# ZYNQ400-CONDIP.net
KiCad netlist of a schematic drawn in Altium Designer
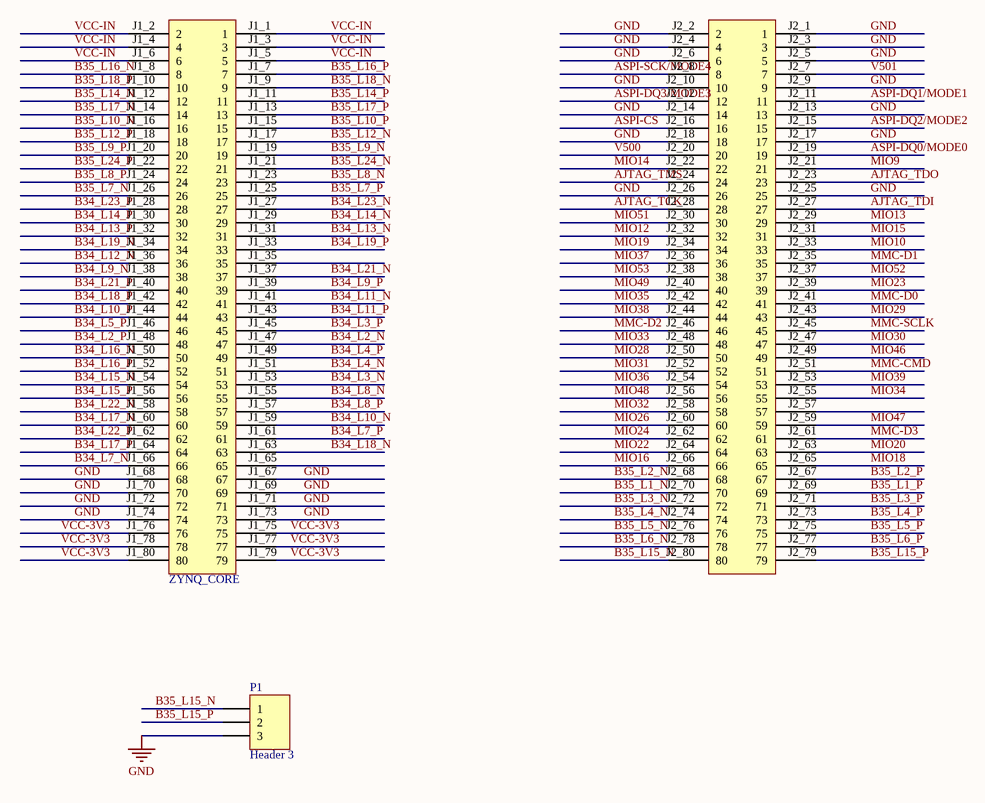
[diagram p0: ZYNQ400-CONDIP.SchDoc]

(export (version "E")
  (design (tool "Eeschema 10.0.6"))
  (components
    (comp (ref "M1")
      (value "ZYNQ_CORE")
      (footprint "ZYNQ7010&7020")
      (description "ZYNQ7010&7020 Core Board")
      (libsource (lib "ZYNQ领航者底板") (part "ZYNQ7010&7020"))
    )
    (comp (ref "P1")
      (value "Header 3")
      (footprint "HDR1X3")
      (description "Header, 3-Pin")
      (fields (field (name "PUBLISHER") "Altium Limited"))
      (libsource (lib "Miscellaneous Connectors") (part "Header 3"))
    )
  )
  (nets
    (net (code "1") (name "/AJTAG_TCK") (class "Default")
      (node (ref "M1") (pin "J2_28") (pinfunction "28_J2_28") (pintype "passive"))
    )
    (net (code "2") (name "/AJTAG_TDI") (class "Default")
      (node (ref "M1") (pin "J2_27") (pinfunction "27_J2_27") (pintype "passive"))
    )
    (net (code "3") (name "/AJTAG_TDO") (class "Default")
      (node (ref "M1") (pin "J2_23") (pinfunction "23_J2_23") (pintype "passive"))
    )
    (net (code "4") (name "/AJTAG_TMS") (class "Default")
      (node (ref "M1") (pin "J2_24") (pinfunction "24_J2_24") (pintype "passive"))
    )
    (net (code "5") (name "/ASPI-CS") (class "Default")
      (node (ref "M1") (pin "J2_16") (pinfunction "16_J2_16") (pintype "passive"))
    )
    (net (code "6") (name "/ASPI-DQ0{slash}MODE0") (class "Default")
      (node (ref "M1") (pin "J2_19") (pinfunction "19_J2_19") (pintype "passive"))
    )
    (net (code "7") (name "/ASPI-DQ1{slash}MODE1") (class "Default")
      (node (ref "M1") (pin "J2_11") (pinfunction "11_J2_11") (pintype "passive"))
    )
    (net (code "8") (name "/ASPI-DQ2{slash}MODE2") (class "Default")
      (node (ref "M1") (pin "J2_15") (pinfunction "15_J2_15") (pintype "passive"))
    )
    (net (code "9") (name "/ASPI-DQ3{slash}MODE3") (class "Default")
      (node (ref "M1") (pin "J2_12") (pinfunction "12_J2_12") (pintype "passive"))
    )
    (net (code "10") (name "/ASPI-SCK{slash}MODE4") (class "Default")
      (node (ref "M1") (pin "J2_8") (pinfunction "8_J2_8") (pintype "passive"))
    )
    (net (code "11") (name "/B34_L2_N") (class "Default")
      (node (ref "M1") (pin "J1_47") (pinfunction "47_J1_47") (pintype "passive"))
    )
    (net (code "12") (name "/B34_L2_P") (class "Default")
      (node (ref "M1") (pin "J1_48") (pinfunction "48_J1_48") (pintype "passive"))
    )
    (net (code "13") (name "/B34_L3_N") (class "Default")
      (node (ref "M1") (pin "J1_53") (pinfunction "53_J1_53") (pintype "passive"))
    )
    (net (code "14") (name "/B34_L3_P") (class "Default")
      (node (ref "M1") (pin "J1_45") (pinfunction "45_J1_45") (pintype "passive"))
    )
    (net (code "15") (name "/B34_L4_N") (class "Default")
      (node (ref "M1") (pin "J1_51") (pinfunction "51_J1_51") (pintype "passive"))
    )
    (net (code "16") (name "/B34_L4_P") (class "Default")
      (node (ref "M1") (pin "J1_49") (pinfunction "49_J1_49") (pintype "passive"))
    )
    (net (code "17") (name "/B34_L5_P") (class "Default")
      (node (ref "M1") (pin "J1_46") (pinfunction "46_J1_46") (pintype "passive"))
    )
    (net (code "18") (name "/B34_L7_N") (class "Default")
      (node (ref "M1") (pin "J1_66") (pinfunction "66_J1_66") (pintype "passive"))
    )
    (net (code "19") (name "/B34_L7_P") (class "Default")
      (node (ref "M1") (pin "J1_61") (pinfunction "61_J1_61") (pintype "passive"))
    )
    (net (code "20") (name "/B34_L8_N") (class "Default")
      (node (ref "M1") (pin "J1_55") (pinfunction "55_J1_55") (pintype "passive"))
    )
    (net (code "21") (name "/B34_L8_P") (class "Default")
      (node (ref "M1") (pin "J1_57") (pinfunction "57_J1_57") (pintype "passive"))
    )
    (net (code "22") (name "/B34_L9_N") (class "Default")
      (node (ref "M1") (pin "J1_38") (pinfunction "38_J1_38") (pintype "passive"))
    )
    (net (code "23") (name "/B34_L9_P") (class "Default")
      (node (ref "M1") (pin "J1_39") (pinfunction "39_J1_39") (pintype "passive"))
    )
    (net (code "24") (name "/B34_L10_N") (class "Default")
      (node (ref "M1") (pin "J1_59") (pinfunction "59_J1_59") (pintype "passive"))
    )
    (net (code "25") (name "/B34_L10_P") (class "Default")
      (node (ref "M1") (pin "J1_44") (pinfunction "44_J1_44") (pintype "passive"))
    )
    (net (code "26") (name "/B34_L11_N") (class "Default")
      (node (ref "M1") (pin "J1_41") (pinfunction "41_J1_41") (pintype "passive"))
    )
    (net (code "27") (name "/B34_L11_P") (class "Default")
      (node (ref "M1") (pin "J1_43") (pinfunction "43_J1_43") (pintype "passive"))
    )
    (net (code "28") (name "/B34_L12_N") (class "Default")
      (node (ref "M1") (pin "J1_36") (pinfunction "36_J1_36") (pintype "passive"))
    )
    (net (code "29") (name "/B34_L13_N") (class "Default")
      (node (ref "M1") (pin "J1_31") (pinfunction "31_J1_31") (pintype "passive"))
    )
    (net (code "30") (name "/B34_L13_P") (class "Default")
      (node (ref "M1") (pin "J1_32") (pinfunction "32_J1_32") (pintype "passive"))
    )
    (net (code "31") (name "/B34_L14_N") (class "Default")
      (node (ref "M1") (pin "J1_29") (pinfunction "29_J1_29") (pintype "passive"))
    )
    (net (code "32") (name "/B34_L14_P") (class "Default")
      (node (ref "M1") (pin "J1_30") (pinfunction "30_J1_30") (pintype "passive"))
    )
    (net (code "33") (name "/B34_L15_N") (class "Default")
      (node (ref "M1") (pin "J1_54") (pinfunction "54_J1_54") (pintype "passive"))
    )
    (net (code "34") (name "/B34_L15_P") (class "Default")
      (node (ref "M1") (pin "J1_56") (pinfunction "56_J1_56") (pintype "passive"))
    )
    (net (code "35") (name "/B34_L16_N") (class "Default")
      (node (ref "M1") (pin "J1_50") (pinfunction "50_J1_50") (pintype "passive"))
    )
    (net (code "36") (name "/B34_L16_P") (class "Default")
      (node (ref "M1") (pin "J1_52") (pinfunction "52_J1_52") (pintype "passive"))
    )
    (net (code "37") (name "/B34_L17_N") (class "Default")
      (node (ref "M1") (pin "J1_60") (pinfunction "60_J1_60") (pintype "passive"))
    )
    (net (code "38") (name "/B34_L17_P") (class "Default")
      (node (ref "M1") (pin "J1_64") (pinfunction "64_J1_64") (pintype "passive"))
    )
    (net (code "39") (name "/B34_L18_N") (class "Default")
      (node (ref "M1") (pin "J1_63") (pinfunction "63_J1_63") (pintype "passive"))
    )
    (net (code "40") (name "/B34_L18_P") (class "Default")
      (node (ref "M1") (pin "J1_42") (pinfunction "42_J1_42") (pintype "passive"))
    )
    (net (code "41") (name "/B34_L19_N") (class "Default")
      (node (ref "M1") (pin "J1_34") (pinfunction "34_J1_34") (pintype "passive"))
    )
    (net (code "42") (name "/B34_L19_P") (class "Default")
      (node (ref "M1") (pin "J1_33") (pinfunction "33_J1_33") (pintype "passive"))
    )
    (net (code "43") (name "/B34_L21_N") (class "Default")
      (node (ref "M1") (pin "J1_37") (pinfunction "37_J1_37") (pintype "passive"))
    )
    (net (code "44") (name "/B34_L21_P") (class "Default")
      (node (ref "M1") (pin "J1_40") (pinfunction "40_J1_40") (pintype "passive"))
    )
    (net (code "45") (name "/B34_L22_N") (class "Default")
      (node (ref "M1") (pin "J1_58") (pinfunction "58_J1_58") (pintype "passive"))
    )
    (net (code "46") (name "/B34_L22_P") (class "Default")
      (node (ref "M1") (pin "J1_62") (pinfunction "62_J1_62") (pintype "passive"))
    )
    (net (code "47") (name "/B34_L23_N") (class "Default")
      (node (ref "M1") (pin "J1_27") (pinfunction "27_J1_27") (pintype "passive"))
    )
    (net (code "48") (name "/B34_L23_P") (class "Default")
      (node (ref "M1") (pin "J1_28") (pinfunction "28_J1_28") (pintype "passive"))
    )
    (net (code "49") (name "/B35_L1_N") (class "Default")
      (node (ref "M1") (pin "J2_70") (pinfunction "70_J2_70") (pintype "passive"))
    )
    (net (code "50") (name "/B35_L1_P") (class "Default")
      (node (ref "M1") (pin "J2_69") (pinfunction "69_J2_69") (pintype "passive"))
    )
    (net (code "51") (name "/B35_L2_N") (class "Default")
      (node (ref "M1") (pin "J2_68") (pinfunction "68_J2_68") (pintype "passive"))
    )
    (net (code "52") (name "/B35_L2_P") (class "Default")
      (node (ref "M1") (pin "J2_67") (pinfunction "67_J2_67") (pintype "passive"))
    )
    (net (code "53") (name "/B35_L3_N") (class "Default")
      (node (ref "M1") (pin "J2_72") (pinfunction "72_J2_72") (pintype "passive"))
    )
    (net (code "54") (name "/B35_L3_P") (class "Default")
      (node (ref "M1") (pin "J2_71") (pinfunction "71_J2_71") (pintype "passive"))
    )
    (net (code "55") (name "/B35_L4_N") (class "Default")
      (node (ref "M1") (pin "J2_74") (pinfunction "74_J2_74") (pintype "passive"))
    )
    (net (code "56") (name "/B35_L4_P") (class "Default")
      (node (ref "M1") (pin "J2_73") (pinfunction "73_J2_73") (pintype "passive"))
    )
    (net (code "57") (name "/B35_L5_N") (class "Default")
      (node (ref "M1") (pin "J2_76") (pinfunction "76_J2_76") (pintype "passive"))
    )
    (net (code "58") (name "/B35_L5_P") (class "Default")
      (node (ref "M1") (pin "J2_75") (pinfunction "75_J2_75") (pintype "passive"))
    )
    (net (code "59") (name "/B35_L6_N") (class "Default")
      (node (ref "M1") (pin "J2_78") (pinfunction "78_J2_78") (pintype "passive"))
    )
    (net (code "60") (name "/B35_L6_P") (class "Default")
      (node (ref "M1") (pin "J2_77") (pinfunction "77_J2_77") (pintype "passive"))
    )
    (net (code "61") (name "/B35_L7_N") (class "Default")
      (node (ref "M1") (pin "J1_26") (pinfunction "26_J1_26") (pintype "passive"))
    )
    (net (code "62") (name "/B35_L7_P") (class "Default")
      (node (ref "M1") (pin "J1_25") (pinfunction "25_J1_25") (pintype "passive"))
    )
    (net (code "63") (name "/B35_L8_N") (class "Default")
      (node (ref "M1") (pin "J1_23") (pinfunction "23_J1_23") (pintype "passive"))
    )
    (net (code "64") (name "/B35_L8_P") (class "Default")
      (node (ref "M1") (pin "J1_24") (pinfunction "24_J1_24") (pintype "passive"))
    )
    (net (code "65") (name "/B35_L9_N") (class "Default")
      (node (ref "M1") (pin "J1_19") (pinfunction "19_J1_19") (pintype "passive"))
    )
    (net (code "66") (name "/B35_L9_P") (class "Default")
      (node (ref "M1") (pin "J1_20") (pinfunction "20_J1_20") (pintype "passive"))
    )
    (net (code "67") (name "/B35_L10_N") (class "Default")
      (node (ref "M1") (pin "J1_16") (pinfunction "16_J1_16") (pintype "passive"))
    )
    (net (code "68") (name "/B35_L10_P") (class "Default")
      (node (ref "M1") (pin "J1_15") (pinfunction "15_J1_15") (pintype "passive"))
    )
    (net (code "69") (name "/B35_L12_N") (class "Default")
      (node (ref "M1") (pin "J1_17") (pinfunction "17_J1_17") (pintype "passive"))
    )
    (net (code "70") (name "/B35_L12_P") (class "Default")
      (node (ref "M1") (pin "J1_18") (pinfunction "18_J1_18") (pintype "passive"))
    )
    (net (code "71") (name "/B35_L14_N") (class "Default")
      (node (ref "M1") (pin "J1_12") (pinfunction "12_J1_12") (pintype "passive"))
    )
    (net (code "72") (name "/B35_L14_P") (class "Default")
      (node (ref "M1") (pin "J1_11") (pinfunction "11_J1_11") (pintype "passive"))
    )
    (net (code "73") (name "/B35_L15_N") (class "Default")
      (node (ref "M1") (pin "J2_80") (pinfunction "80_J2_80") (pintype "passive"))
      (node (ref "P1") (pin "1") (pinfunction "1_1") (pintype "passive"))
    )
    (net (code "74") (name "/B35_L15_P") (class "Default")
      (node (ref "M1") (pin "J2_79") (pinfunction "79_J2_79") (pintype "passive"))
      (node (ref "P1") (pin "2") (pinfunction "2_2") (pintype "passive"))
    )
    (net (code "75") (name "/B35_L16_N") (class "Default")
      (node (ref "M1") (pin "J1_8") (pinfunction "8_J1_8") (pintype "passive"))
    )
    (net (code "76") (name "/B35_L16_P") (class "Default")
      (node (ref "M1") (pin "J1_7") (pinfunction "7_J1_7") (pintype "passive"))
    )
    (net (code "77") (name "/B35_L17_N") (class "Default")
      (node (ref "M1") (pin "J1_14") (pinfunction "14_J1_14") (pintype "passive"))
    )
    (net (code "78") (name "/B35_L17_P") (class "Default")
      (node (ref "M1") (pin "J1_13") (pinfunction "13_J1_13") (pintype "passive"))
    )
    (net (code "79") (name "/B35_L18_N") (class "Default")
      (node (ref "M1") (pin "J1_9") (pinfunction "9_J1_9") (pintype "passive"))
    )
    (net (code "80") (name "/B35_L18_P") (class "Default")
      (node (ref "M1") (pin "J1_10") (pinfunction "10_J1_10") (pintype "passive"))
    )
    (net (code "81") (name "/B35_L24_N") (class "Default")
      (node (ref "M1") (pin "J1_21") (pinfunction "21_J1_21") (pintype "passive"))
    )
    (net (code "82") (name "/B35_L24_P") (class "Default")
      (node (ref "M1") (pin "J1_22") (pinfunction "22_J1_22") (pintype "passive"))
    )
    (net (code "83") (name "/MIO9") (class "Default")
      (node (ref "M1") (pin "J2_21") (pinfunction "21_J2_21") (pintype "passive"))
    )
    (net (code "84") (name "/MIO10") (class "Default")
      (node (ref "M1") (pin "J2_33") (pinfunction "33_J2_33") (pintype "passive"))
    )
    (net (code "85") (name "/MIO12") (class "Default")
      (node (ref "M1") (pin "J2_32") (pinfunction "32_J2_32") (pintype "passive"))
    )
    (net (code "86") (name "/MIO13") (class "Default")
      (node (ref "M1") (pin "J2_29") (pinfunction "29_J2_29") (pintype "passive"))
    )
    (net (code "87") (name "/MIO14") (class "Default")
      (node (ref "M1") (pin "J2_22") (pinfunction "22_J2_22") (pintype "passive"))
    )
    (net (code "88") (name "/MIO15") (class "Default")
      (node (ref "M1") (pin "J2_31") (pinfunction "31_J2_31") (pintype "passive"))
    )
    (net (code "89") (name "/MIO16") (class "Default")
      (node (ref "M1") (pin "J2_66") (pinfunction "66_J2_66") (pintype "passive"))
    )
    (net (code "90") (name "/MIO18") (class "Default")
      (node (ref "M1") (pin "J2_65") (pinfunction "65_J2_65") (pintype "passive"))
    )
    (net (code "91") (name "/MIO19") (class "Default")
      (node (ref "M1") (pin "J2_34") (pinfunction "34_J2_34") (pintype "passive"))
    )
    (net (code "92") (name "/MIO20") (class "Default")
      (node (ref "M1") (pin "J2_63") (pinfunction "63_J2_63") (pintype "passive"))
    )
    (net (code "93") (name "/MIO22") (class "Default")
      (node (ref "M1") (pin "J2_64") (pinfunction "64_J2_64") (pintype "passive"))
    )
    (net (code "94") (name "/MIO23") (class "Default")
      (node (ref "M1") (pin "J2_39") (pinfunction "39_J2_39") (pintype "passive"))
    )
    (net (code "95") (name "/MIO24") (class "Default")
      (node (ref "M1") (pin "J2_62") (pinfunction "62_J2_62") (pintype "passive"))
    )
    (net (code "96") (name "/MIO26") (class "Default")
      (node (ref "M1") (pin "J2_60") (pinfunction "60_J2_60") (pintype "passive"))
    )
    (net (code "97") (name "/MIO28") (class "Default")
      (node (ref "M1") (pin "J2_50") (pinfunction "50_J2_50") (pintype "passive"))
    )
    (net (code "98") (name "/MIO29") (class "Default")
      (node (ref "M1") (pin "J2_43") (pinfunction "43_J2_43") (pintype "passive"))
    )
    (net (code "99") (name "/MIO30") (class "Default")
      (node (ref "M1") (pin "J2_47") (pinfunction "47_J2_47") (pintype "passive"))
    )
    (net (code "100") (name "/MIO31") (class "Default")
      (node (ref "M1") (pin "J2_52") (pinfunction "52_J2_52") (pintype "passive"))
    )
    (net (code "101") (name "/MIO32") (class "Default")
      (node (ref "M1") (pin "J2_58") (pinfunction "58_J2_58") (pintype "passive"))
    )
    (net (code "102") (name "/MIO33") (class "Default")
      (node (ref "M1") (pin "J2_48") (pinfunction "48_J2_48") (pintype "passive"))
    )
    (net (code "103") (name "/MIO34") (class "Default")
      (node (ref "M1") (pin "J2_55") (pinfunction "55_J2_55") (pintype "passive"))
    )
    (net (code "104") (name "/MIO35") (class "Default")
      (node (ref "M1") (pin "J2_42") (pinfunction "42_J2_42") (pintype "passive"))
    )
    (net (code "105") (name "/MIO36") (class "Default")
      (node (ref "M1") (pin "J2_54") (pinfunction "54_J2_54") (pintype "passive"))
    )
    (net (code "106") (name "/MIO37") (class "Default")
      (node (ref "M1") (pin "J2_36") (pinfunction "36_J2_36") (pintype "passive"))
    )
    (net (code "107") (name "/MIO38") (class "Default")
      (node (ref "M1") (pin "J2_44") (pinfunction "44_J2_44") (pintype "passive"))
    )
    (net (code "108") (name "/MIO39") (class "Default")
      (node (ref "M1") (pin "J2_53") (pinfunction "53_J2_53") (pintype "passive"))
    )
    (net (code "109") (name "/MIO46") (class "Default")
      (node (ref "M1") (pin "J2_49") (pinfunction "49_J2_49") (pintype "passive"))
    )
    (net (code "110") (name "/MIO47") (class "Default")
      (node (ref "M1") (pin "J2_59") (pinfunction "59_J2_59") (pintype "passive"))
    )
    (net (code "111") (name "/MIO48") (class "Default")
      (node (ref "M1") (pin "J2_56") (pinfunction "56_J2_56") (pintype "passive"))
    )
    (net (code "112") (name "/MIO49") (class "Default")
      (node (ref "M1") (pin "J2_40") (pinfunction "40_J2_40") (pintype "passive"))
    )
    (net (code "113") (name "/MIO51") (class "Default")
      (node (ref "M1") (pin "J2_30") (pinfunction "30_J2_30") (pintype "passive"))
    )
    (net (code "114") (name "/MIO52") (class "Default")
      (node (ref "M1") (pin "J2_37") (pinfunction "37_J2_37") (pintype "passive"))
    )
    (net (code "115") (name "/MIO53") (class "Default")
      (node (ref "M1") (pin "J2_38") (pinfunction "38_J2_38") (pintype "passive"))
    )
    (net (code "116") (name "/MMC-CMD") (class "Default")
      (node (ref "M1") (pin "J2_51") (pinfunction "51_J2_51") (pintype "passive"))
    )
    (net (code "117") (name "/MMC-D0") (class "Default")
      (node (ref "M1") (pin "J2_41") (pinfunction "41_J2_41") (pintype "passive"))
    )
    (net (code "118") (name "/MMC-D1") (class "Default")
      (node (ref "M1") (pin "J2_35") (pinfunction "35_J2_35") (pintype "passive"))
    )
    (net (code "119") (name "/MMC-D2") (class "Default")
      (node (ref "M1") (pin "J2_46") (pinfunction "46_J2_46") (pintype "passive"))
    )
    (net (code "120") (name "/MMC-D3") (class "Default")
      (node (ref "M1") (pin "J2_61") (pinfunction "61_J2_61") (pintype "passive"))
    )
    (net (code "121") (name "/MMC-SCLK") (class "Default")
      (node (ref "M1") (pin "J2_45") (pinfunction "45_J2_45") (pintype "passive"))
    )
    (net (code "122") (name "/V500") (class "Default")
      (node (ref "M1") (pin "J2_20") (pinfunction "20_J2_20") (pintype "passive"))
    )
    (net (code "123") (name "/V501") (class "Default")
      (node (ref "M1") (pin "J2_7") (pinfunction "7_J2_7") (pintype "passive"))
    )
    (net (code "124") (name "/VCC-3V3") (class "Default")
      (node (ref "M1") (pin "J1_75") (pinfunction "75_J1_75") (pintype "passive"))
      (node (ref "M1") (pin "J1_76") (pinfunction "76_J1_76") (pintype "passive"))
      (node (ref "M1") (pin "J1_77") (pinfunction "77_J1_77") (pintype "passive"))
      (node (ref "M1") (pin "J1_78") (pinfunction "78_J1_78") (pintype "passive"))
      (node (ref "M1") (pin "J1_79") (pinfunction "79_J1_79") (pintype "passive"))
      (node (ref "M1") (pin "J1_80") (pinfunction "80_J1_80") (pintype "passive"))
    )
    (net (code "125") (name "/VCC-IN") (class "Default")
      (node (ref "M1") (pin "J1_1") (pinfunction "1_J1_1") (pintype "passive"))
      (node (ref "M1") (pin "J1_2") (pinfunction "2_J1_2") (pintype "passive"))
      (node (ref "M1") (pin "J1_3") (pinfunction "3_J1_3") (pintype "passive"))
      (node (ref "M1") (pin "J1_4") (pinfunction "4_J1_4") (pintype "passive"))
      (node (ref "M1") (pin "J1_5") (pinfunction "5_J1_5") (pintype "passive"))
      (node (ref "M1") (pin "J1_6") (pinfunction "6_J1_6") (pintype "passive"))
    )
    (net (code "126") (name "GND") (class "Default")
      (node (ref "M1") (pin "J1_67") (pinfunction "67_J1_67") (pintype "passive"))
      (node (ref "M1") (pin "J1_68") (pinfunction "68_J1_68") (pintype "passive"))
      (node (ref "M1") (pin "J1_69") (pinfunction "69_J1_69") (pintype "passive"))
      (node (ref "M1") (pin "J1_70") (pinfunction "70_J1_70") (pintype "passive"))
      (node (ref "M1") (pin "J1_71") (pinfunction "71_J1_71") (pintype "passive"))
      (node (ref "M1") (pin "J1_72") (pinfunction "72_J1_72") (pintype "passive"))
      (node (ref "M1") (pin "J1_73") (pinfunction "73_J1_73") (pintype "passive"))
      (node (ref "M1") (pin "J1_74") (pinfunction "74_J1_74") (pintype "passive"))
      (node (ref "M1") (pin "J2_1") (pinfunction "1_J2_1") (pintype "passive"))
      (node (ref "M1") (pin "J2_10") (pinfunction "10_J2_10") (pintype "passive"))
      (node (ref "M1") (pin "J2_13") (pinfunction "13_J2_13") (pintype "passive"))
      (node (ref "M1") (pin "J2_14") (pinfunction "14_J2_14") (pintype "passive"))
      (node (ref "M1") (pin "J2_17") (pinfunction "17_J2_17") (pintype "passive"))
      (node (ref "M1") (pin "J2_18") (pinfunction "18_J2_18") (pintype "passive"))
      (node (ref "M1") (pin "J2_2") (pinfunction "2_J2_2") (pintype "passive"))
      (node (ref "M1") (pin "J2_25") (pinfunction "25_J2_25") (pintype "passive"))
      (node (ref "M1") (pin "J2_26") (pinfunction "26_J2_26") (pintype "passive"))
      (node (ref "M1") (pin "J2_3") (pinfunction "3_J2_3") (pintype "passive"))
      (node (ref "M1") (pin "J2_4") (pinfunction "4_J2_4") (pintype "passive"))
      (node (ref "M1") (pin "J2_5") (pinfunction "5_J2_5") (pintype "passive"))
      (node (ref "M1") (pin "J2_6") (pinfunction "6_J2_6") (pintype "passive"))
      (node (ref "M1") (pin "J2_9") (pinfunction "9_J2_9") (pintype "passive"))
      (node (ref "P1") (pin "3") (pinfunction "3_3") (pintype "passive"))
    )
    (net (code "127") (name "unconnected-(M1-35-PadJ1_35)") (class "Default")
      (node (ref "M1") (pin "J1_35") (pinfunction "35_J1_35") (pintype "passive"))
    )
    (net (code "128") (name "unconnected-(M1-57-PadJ2_57)") (class "Default")
      (node (ref "M1") (pin "J2_57") (pinfunction "57_J2_57") (pintype "passive"))
    )
    (net (code "129") (name "unconnected-(M1-65-PadJ1_65)") (class "Default")
      (node (ref "M1") (pin "J1_65") (pinfunction "65_J1_65") (pintype "passive"))
    )
  )
)
